# Chargers.net
KiCad netlist of a schematic drawn in Altium Designer
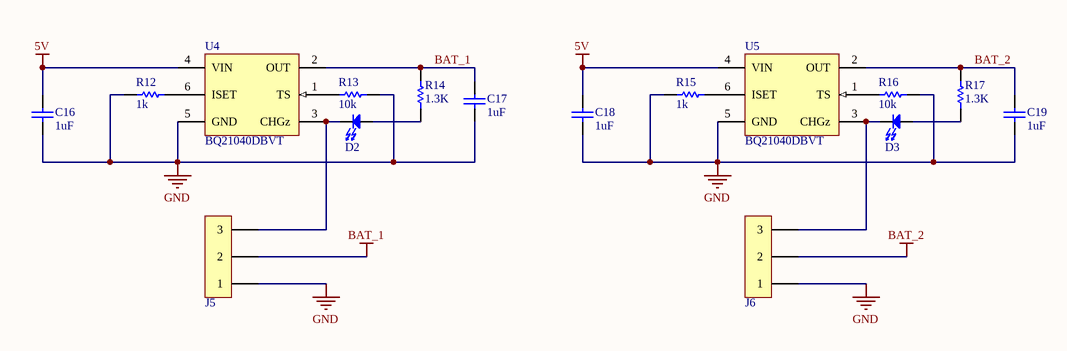
[diagram p0: Chargers.SchDoc]

(export (version "E")
  (design (tool "Eeschema 10.0.6"))
  (components
    (comp (ref "C16")
      (value "1uF")
      (footprint "CAPC1608X09N")
      (fields
        (field (name "DIGIKEY PART NUMBER") "490-10487-1-ND")
        (field (name "VOLTAGE") "35V")
        (field (name "MANUFACTURER") "Murata")
      )
      (libsource (lib "Speaker Library") (part "CAP CER 1uF 0603"))
    )
    (comp (ref "C17")
      (value "1uF")
      (footprint "CAPC1608X09N")
      (fields
        (field (name "DIGIKEY PART NUMBER") "490-10487-1-ND")
        (field (name "VOLTAGE") "35V")
        (field (name "MANUFACTURER") "Murata")
      )
      (libsource (lib "Speaker Library") (part "CAP CER 1uF 0603"))
    )
    (comp (ref "C18")
      (value "1uF")
      (footprint "CAPC1608X09N")
      (fields
        (field (name "DIGIKEY PART NUMBER") "490-10487-1-ND")
        (field (name "VOLTAGE") "35V")
        (field (name "MANUFACTURER") "Murata")
      )
      (libsource (lib "Speaker Library") (part "CAP CER 1uF 0603"))
    )
    (comp (ref "C19")
      (value "1uF")
      (footprint "CAPC1608X09N")
      (fields
        (field (name "DIGIKEY PART NUMBER") "490-10487-1-ND")
        (field (name "VOLTAGE") "35V")
        (field (name "MANUFACTURER") "Murata")
      )
      (libsource (lib "Speaker Library") (part "CAP CER 1uF 0603"))
    )
    (comp (ref "D2")
      (value "LED 0603")
      (footprint "DIOM1608X08N")
      (fields (field (name "VOLTAGE") "2.2V") (field (name "DIGIKEY PART NUMBER") "160-1447-1-ND"))
      (libsource (lib "Speaker Library") (part "LED 0603"))
    )
    (comp (ref "D3")
      (value "LED 0603")
      (footprint "DIOM1608X08N")
      (fields (field (name "VOLTAGE") "2.2V") (field (name "DIGIKEY PART NUMBER") "160-1447-1-ND"))
      (libsource (lib "Speaker Library") (part "LED 0603"))
    )
    (comp (ref "J5")
      (value "3POS THRU HOLE 2.54MM")
      (footprint "3POS Through Hole 2.54MM")
      (libsource (lib "Speaker Library") (part "3POS THRU HOLE 2.54MM"))
    )
    (comp (ref "J6")
      (value "3POS THRU HOLE 2.54MM")
      (footprint "3POS Through Hole 2.54MM")
      (libsource (lib "Speaker Library") (part "3POS THRU HOLE 2.54MM"))
    )
    (comp (ref "R12")
      (value "1k")
      (footprint "RESC1608X06N")
      (fields
        (field (name "TOLERANCE") "1%")
        (field (name "POWER") "0.25W")
        (field (name "MANUFACTURER") "Panasonic")
      )
      (libsource (lib "Speaker Library") (part "RES 1K 0603"))
    )
    (comp (ref "R13")
      (value "10k")
      (footprint "RESC1608X06N")
      (fields
        (field (name "TOLERANCE") "1%")
        (field (name "POWER") "0.1W")
        (field (name "MANUFACTURER") "Yageo")
      )
      (libsource (lib "Speaker Library") (part "RES 10K 0603"))
    )
    (comp (ref "R14")
      (value "1.3K")
      (footprint "RESC1608X06N")
      (fields
        (field (name "TOLERANCE") "1%")
        (field (name "POWER") "0.1W")
        (field (name "MANUFACTURER") "Vishay Dale")
      )
      (libsource (lib "Speaker Library") (part "RES 1.3K 0603"))
    )
    (comp (ref "R15")
      (value "1k")
      (footprint "RESC1608X06N")
      (fields
        (field (name "TOLERANCE") "1%")
        (field (name "POWER") "0.25W")
        (field (name "MANUFACTURER") "Panasonic")
      )
      (libsource (lib "Speaker Library") (part "RES 1K 0603"))
    )
    (comp (ref "R16")
      (value "10k")
      (footprint "RESC1608X06N")
      (fields
        (field (name "TOLERANCE") "1%")
        (field (name "POWER") "0.1W")
        (field (name "MANUFACTURER") "Yageo")
      )
      (libsource (lib "Speaker Library") (part "RES 10K 0603"))
    )
    (comp (ref "R17")
      (value "1.3K")
      (footprint "RESC1608X06N")
      (fields
        (field (name "TOLERANCE") "1%")
        (field (name "POWER") "0.1W")
        (field (name "MANUFACTURER") "Vishay Dale")
      )
      (libsource (lib "Speaker Library") (part "RES 1.3K 0603"))
    )
    (comp (ref "U4")
      (value "BQ21040DBVT")
      (footprint "SOT95P280X145-6N (DBV)")
      (description "Charger, Li-Ion, SOT-23-6")
      (fields
        (field (name "MANUFACTURER") "Texas Instruments")
        (field (name "DIGIKEY PART NUMBER") "296-44196-1-ND")
      )
      (libsource (lib "Speaker Library") (part "BQ21040DBVT"))
    )
    (comp (ref "U5")
      (value "BQ21040DBVT")
      (footprint "SOT95P280X145-6N (DBV)")
      (description "Charger, Li-Ion, SOT-23-6")
      (fields
        (field (name "MANUFACTURER") "Texas Instruments")
        (field (name "DIGIKEY PART NUMBER") "296-44196-1-ND")
      )
      (libsource (lib "Speaker Library") (part "BQ21040DBVT"))
    )
  )
  (nets
    (net (code "1") (name "5V") (class "Default")
      (node (ref "C16") (pin "2") (pinfunction "2_2") (pintype "passive"))
      (node (ref "C18") (pin "2") (pinfunction "2_2") (pintype "passive"))
      (node (ref "U4") (pin "4") (pinfunction "VIN_4") (pintype "power_in"))
      (node (ref "U5") (pin "4") (pinfunction "VIN_4") (pintype "power_in"))
    )
    (net (code "2") (name "BAT_1") (class "Default")
      (node (ref "C17") (pin "2") (pinfunction "2_2") (pintype "passive"))
      (node (ref "J5") (pin "2") (pinfunction "2_2") (pintype "passive"))
      (node (ref "R14") (pin "2") (pinfunction "2_2") (pintype "passive"))
      (node (ref "U4") (pin "2") (pinfunction "OUT_2") (pintype "passive"))
    )
    (net (code "3") (name "BAT_2") (class "Default")
      (node (ref "C19") (pin "2") (pinfunction "2_2") (pintype "passive"))
      (node (ref "J6") (pin "2") (pinfunction "2_2") (pintype "passive"))
      (node (ref "R17") (pin "2") (pinfunction "2_2") (pintype "passive"))
      (node (ref "U5") (pin "2") (pinfunction "OUT_2") (pintype "passive"))
    )
    (net (code "4") (name "GND") (class "Default")
      (node (ref "C16") (pin "1") (pinfunction "1_1") (pintype "passive"))
      (node (ref "C17") (pin "1") (pinfunction "1_1") (pintype "passive"))
      (node (ref "C18") (pin "1") (pinfunction "1_1") (pintype "passive"))
      (node (ref "C19") (pin "1") (pinfunction "1_1") (pintype "passive"))
      (node (ref "J5") (pin "1") (pinfunction "1_1") (pintype "passive"))
      (node (ref "J6") (pin "1") (pinfunction "1_1") (pintype "passive"))
      (node (ref "R12") (pin "1") (pinfunction "1_1") (pintype "passive"))
      (node (ref "R13") (pin "2") (pinfunction "2_2") (pintype "passive"))
      (node (ref "R15") (pin "1") (pinfunction "1_1") (pintype "passive"))
      (node (ref "R16") (pin "2") (pinfunction "2_2") (pintype "passive"))
      (node (ref "U4") (pin "5") (pinfunction "GND_5") (pintype "power_in"))
      (node (ref "U5") (pin "5") (pinfunction "GND_5") (pintype "power_in"))
    )
    (net (code "5") (name "Net-(D2-A2)") (class "Default")
      (node (ref "D2") (pin "2") (pinfunction "A2_2") (pintype "passive"))
      (node (ref "R14") (pin "1") (pinfunction "1_1") (pintype "passive"))
    )
    (net (code "6") (name "Net-(D2-K2)") (class "Default")
      (node (ref "D2") (pin "1") (pinfunction "K2_1") (pintype "passive"))
      (node (ref "J5") (pin "3") (pinfunction "3_3") (pintype "passive"))
      (node (ref "U4") (pin "3") (pinfunction "CHGz_3") (pintype "passive"))
    )
    (net (code "7") (name "Net-(D3-A2)") (class "Default")
      (node (ref "D3") (pin "2") (pinfunction "A2_2") (pintype "passive"))
      (node (ref "R17") (pin "1") (pinfunction "1_1") (pintype "passive"))
    )
    (net (code "8") (name "Net-(D3-K2)") (class "Default")
      (node (ref "D3") (pin "1") (pinfunction "K2_1") (pintype "passive"))
      (node (ref "J6") (pin "3") (pinfunction "3_3") (pintype "passive"))
      (node (ref "U5") (pin "3") (pinfunction "CHGz_3") (pintype "passive"))
    )
    (net (code "9") (name "Net-(U4-ISET)") (class "Default")
      (node (ref "R12") (pin "2") (pinfunction "2_2") (pintype "passive"))
      (node (ref "U4") (pin "6") (pinfunction "ISET_6") (pintype "passive"))
    )
    (net (code "10") (name "Net-(U4-TS)") (class "Default")
      (node (ref "R13") (pin "1") (pinfunction "1_1") (pintype "passive"))
      (node (ref "U4") (pin "1") (pinfunction "TS_1") (pintype "input"))
    )
    (net (code "11") (name "Net-(U5-ISET)") (class "Default")
      (node (ref "R15") (pin "2") (pinfunction "2_2") (pintype "passive"))
      (node (ref "U5") (pin "6") (pinfunction "ISET_6") (pintype "passive"))
    )
    (net (code "12") (name "Net-(U5-TS)") (class "Default")
      (node (ref "R16") (pin "1") (pinfunction "1_1") (pintype "passive"))
      (node (ref "U5") (pin "1") (pinfunction "TS_1") (pintype "input"))
    )
  )
)
